# STM_Bluetooth.net
KiCad netlist of a schematic drawn in Altium Designer
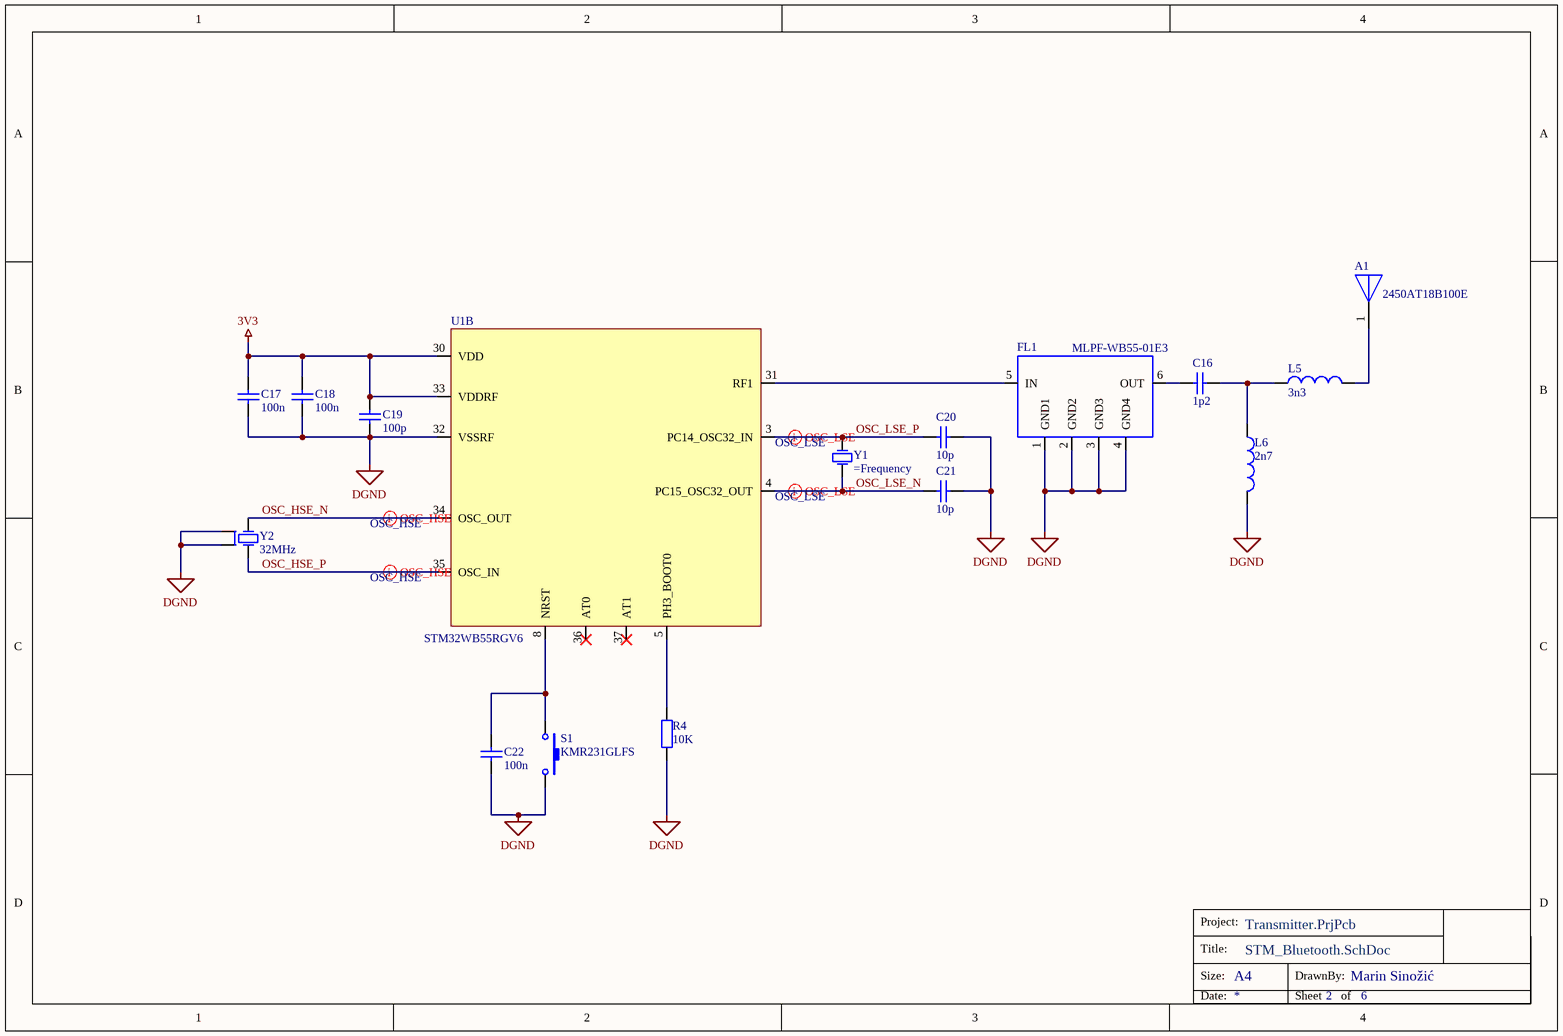
[diagram p0: STM_Bluetooth.SchDoc]

(export (version "E")
  (design (tool "Eeschema 10.0.6"))
  (components
    (comp (ref "A1")
      (value "2450AT18B100E")
      (footprint "ANT_2450AT18B100E")
      (description "RF ANT 2.4GHZ CHIP SOLDER SMD")
      (fields (field (name "MANUFACTURER PART NUMBER") "712-1006-1-ND"))
      (libsource (lib "Tx_board") (part "BT_ANTENNA"))
    )
    (comp (ref "C16")
      (value "1p2")
      (footprint "0402")
      (description "CAP CER 1.2PF 50V C0G/NP0 0402")
      (fields (field (name "MANUFACTURER PART NUMBER") "712-1268-1-ND"))
      (libsource (lib "Miscellaneous Devices") (part "Cap"))
    )
    (comp (ref "C17")
      (value "100n")
      (footprint "0603")
      (description "CAP CER 0.1UF 50V X7R 0603")
      (fields (field (name "MANUFACTURER PART NUMBER") "1276-CL10B104KB8WPNDCT-ND"))
      (libsource (lib "Miscellaneous Devices") (part "Cap"))
    )
    (comp (ref "C18")
      (value "100n")
      (footprint "0603")
      (description "CAP CER 0.1UF 50V X7R 0603")
      (fields (field (name "MANUFACTURER PART NUMBER") "1276-CL10B104KB8WPNDCT-ND"))
      (libsource (lib "Miscellaneous Devices") (part "Cap"))
    )
    (comp (ref "C19")
      (value "100p")
      (footprint "0603")
      (description "CAP CER 100PF 50V X7R 0603")
      (fields (field (name "MANUFACTURER PART NUMBER") "1276-1908-1-ND"))
      (libsource (lib "Miscellaneous Devices") (part "Cap"))
    )
    (comp (ref "C20")
      (value "10p")
      (footprint "0603")
      (description "CAP CER 10PF 50V X7R 0603")
      (fields (field (name "MANUFACTURER PART NUMBER") "399-C0603C100J5RAC7867CT-ND"))
      (libsource (lib "Miscellaneous Devices") (part "Cap"))
    )
    (comp (ref "C21")
      (value "10p")
      (footprint "0603")
      (description "CAP CER 10PF 50V X7R 0603")
      (fields (field (name "MANUFACTURER PART NUMBER") "399-C0603C100J5RAC7867CT-ND"))
      (libsource (lib "Miscellaneous Devices") (part "Cap"))
    )
    (comp (ref "C22")
      (value "100n")
      (footprint "0603")
      (description "CAP CER 0.1UF 50V X7R 0603")
      (fields (field (name "MANUFACTURER PART NUMBER") "1276-CL10B104KB8WPNDCT-ND"))
      (libsource (lib "Miscellaneous Devices") (part "Cap"))
    )
    (comp (ref "FL1")
      (value "MLPF-WB55-01E3")
      (footprint "CSP_BUMPLESS")
      (description "RF Filter Low Pass 2400MHz to 2500MHz 1.1dB 50Ohm SMD 6Pin T/R")
      (libsource (lib "Tx_board") (part "FLT_2.4GHz"))
    )
    (comp (ref "L5")
      (value "3n3")
      (footprint "0402")
      (description "FIXED IND 3.3NH 300MA 190MOHM SM")
      (fields (field (name "MANUFACTURER PART NUMBER") "712-1416-1-ND"))
      (libsource (lib "Tx_board") (part "L_0805_10uH"))
    )
    (comp (ref "L6")
      (value "2n7")
      (footprint "0402")
      (description "FIXED IND 2.7NH 300MA 170MOHM SM")
      (fields (field (name "MANUFACTURER PART NUMBER") "712-1415-1-ND"))
      (libsource (lib "Tx_board") (part "L_0805_10uH"))
    )
    (comp (ref "R4")
      (value "10K")
      (footprint "0603")
      (description "RES SMD 10K OHM 0.5% 1/5W 0603")
      (fields (field (name "MANUFACTURER PART NUMBER") "P20397CT-ND"))
      (libsource (lib "Miscellaneous Devices") (part "Res2"))
    )
    (comp (ref "S1")
      (value "KMR231GLFS")
      (footprint "SW-PB SMD KMR2")
      (description "Switch Tactile N.O. SPST Button Gull Wing 0.05A 32VDC 1VA 150000Cycles 3N SMD T/R")
      (fields (field (name "MANUFACTURER PART NUMBER") "1437636"))
      (libsource (lib "Tx_board") (part "SW-PB"))
    )
    (comp (ref "U1")
      (value "STM32WB55RGV6")
      (footprint "STM32WB55RGV7:Model Name")
      (description "MCU 32-Bit STM32WB55 ARM Cortex M4 RISC 1MB Flash 1.7V to 3.6V 68-Pin VFQFPN Tray")
      (libsource (lib "Transmitter") (part "STM32WB55RGV6"))
    )
    (comp (ref "Y1")
      (value "~")
      (footprint "NX2012_2P")
      (description "NDK 32.76kHz Crystal Unit ±20ppm SMD 2-Pin 2.05 x 1.2 x 0.55mm")
      (fields (field (name "MANUFACTURER PART NUMBER") "644-1219-1-ND"))
      (libsource (lib "Tx_board") (part "OSC_LFXTAL073170_32.768kHz"))
    )
    (comp (ref "Y2")
      (value "32MHz")
      (footprint "NX2016_4P")
      (description "Crystal 32.0MHZ 10PF SMD Esr 60")
      (fields (field (name "MANUFACTURER PART NUMBER") "1923-1603-1-ND"))
      (libsource (lib "Tx_board") (part "OSC_LFXTAL073170_32MHz"))
    )
  )
  (nets
    (net (code "1") (name "/OSC_HSE_N") (class "Default")
      (node (ref "U1") (pin "34") (pinfunction "OSC_OUT_34") (pintype "passive"))
      (node (ref "Y2") (pin "1") (pinfunction "OSC1_1") (pintype "passive"))
    )
    (net (code "2") (name "/OSC_HSE_P") (class "Default")
      (node (ref "U1") (pin "35") (pinfunction "OSC_IN_35") (pintype "passive"))
      (node (ref "Y2") (pin "3") (pinfunction "OSC2_3") (pintype "passive"))
    )
    (net (code "3") (name "/OSC_LSE_N") (class "Default")
      (node (ref "C21") (pin "1") (pinfunction "1_1") (pintype "passive"))
      (node (ref "U1") (pin "4") (pinfunction "PC15_OSC32_OUT_4") (pintype "passive"))
      (node (ref "Y1") (pin "1") (pinfunction "OSC1_1") (pintype "passive"))
    )
    (net (code "4") (name "/OSC_LSE_P") (class "Default")
      (node (ref "C20") (pin "1") (pinfunction "1_1") (pintype "passive"))
      (node (ref "U1") (pin "3") (pinfunction "PC14_OSC32_IN_3") (pintype "passive"))
      (node (ref "Y1") (pin "2") (pinfunction "OSC2_2") (pintype "passive"))
    )
    (net (code "5") (name "3V3") (class "Default")
      (node (ref "C17") (pin "2") (pinfunction "2_2") (pintype "passive"))
      (node (ref "C18") (pin "2") (pinfunction "2_2") (pintype "passive"))
      (node (ref "C19") (pin "2") (pinfunction "2_2") (pintype "passive"))
      (node (ref "U1") (pin "30") (pinfunction "VDD_30") (pintype "power_in"))
      (node (ref "U1") (pin "33") (pinfunction "VDDRF_33") (pintype "power_in"))
    )
    (net (code "6") (name "DGND") (class "Default")
      (node (ref "C17") (pin "1") (pinfunction "1_1") (pintype "passive"))
      (node (ref "C18") (pin "1") (pinfunction "1_1") (pintype "passive"))
      (node (ref "C19") (pin "1") (pinfunction "1_1") (pintype "passive"))
      (node (ref "C20") (pin "2") (pinfunction "2_2") (pintype "passive"))
      (node (ref "C21") (pin "2") (pinfunction "2_2") (pintype "passive"))
      (node (ref "C22") (pin "1") (pinfunction "1_1") (pintype "passive"))
      (node (ref "FL1") (pin "1") (pinfunction "GND1_1") (pintype "power_in"))
      (node (ref "FL1") (pin "2") (pinfunction "GND2_2") (pintype "power_in"))
      (node (ref "FL1") (pin "3") (pinfunction "GND3_3") (pintype "power_in"))
      (node (ref "FL1") (pin "4") (pinfunction "GND4_4") (pintype "power_in"))
      (node (ref "L6") (pin "2") (pinfunction "2_2") (pintype "passive"))
      (node (ref "R4") (pin "1") (pinfunction "1_1") (pintype "passive"))
      (node (ref "S1") (pin "2") (pinfunction "2_2") (pintype "passive"))
      (node (ref "U1") (pin "32") (pinfunction "VSSRF_32") (pintype "power_in"))
      (node (ref "Y2") (pin "2") (pinfunction "2_2") (pintype "passive"))
      (node (ref "Y2") (pin "4") (pinfunction "4_4") (pintype "passive"))
    )
    (net (code "7") (name "Net-(A1-Pad1)") (class "Default")
      (node (ref "A1") (pin "1") (pinfunction "1_1") (pintype "passive"))
      (node (ref "L5") (pin "2") (pinfunction "2_2") (pintype "passive"))
    )
    (net (code "8") (name "Net-(C16-Pad1)") (class "Default")
      (node (ref "C16") (pin "1") (pinfunction "1_1") (pintype "passive"))
      (node (ref "L5") (pin "1") (pinfunction "1_1") (pintype "passive"))
      (node (ref "L6") (pin "1") (pinfunction "1_1") (pintype "passive"))
    )
    (net (code "9") (name "Net-(FL1-IN)") (class "Default")
      (node (ref "FL1") (pin "5") (pinfunction "IN_5") (pintype "passive"))
      (node (ref "U1") (pin "31") (pinfunction "RF1_31") (pintype "passive"))
    )
    (net (code "10") (name "Net-(FL1-OUT)") (class "Default")
      (node (ref "C16") (pin "2") (pinfunction "2_2") (pintype "passive"))
      (node (ref "FL1") (pin "6") (pinfunction "OUT_6") (pintype "passive"))
    )
    (net (code "11") (name "Net-(U1B-NRST)") (class "Default")
      (node (ref "C22") (pin "2") (pinfunction "2_2") (pintype "passive"))
      (node (ref "S1") (pin "1") (pinfunction "1_1") (pintype "passive"))
      (node (ref "U1") (pin "8") (pinfunction "NRST_8") (pintype "passive"))
    )
    (net (code "12") (name "Net-(U1B-PH3_BOOT0)") (class "Default")
      (node (ref "R4") (pin "2") (pinfunction "2_2") (pintype "passive"))
      (node (ref "U1") (pin "5") (pinfunction "PH3_BOOT0_5") (pintype "passive"))
    )
    (net (code "13") (name "unconnected-(U1B-AT0-Pad36)") (class "Default")
      (node (ref "U1") (pin "36") (pinfunction "AT0_36") (pintype "passive+no_connect"))
    )
    (net (code "14") (name "unconnected-(U1B-AT1-Pad37)") (class "Default")
      (node (ref "U1") (pin "37") (pinfunction "AT1_37") (pintype "passive+no_connect"))
    )
  )
)
